# USB_Adapter.net
KiCad netlist of a schematic drawn in EAGLE
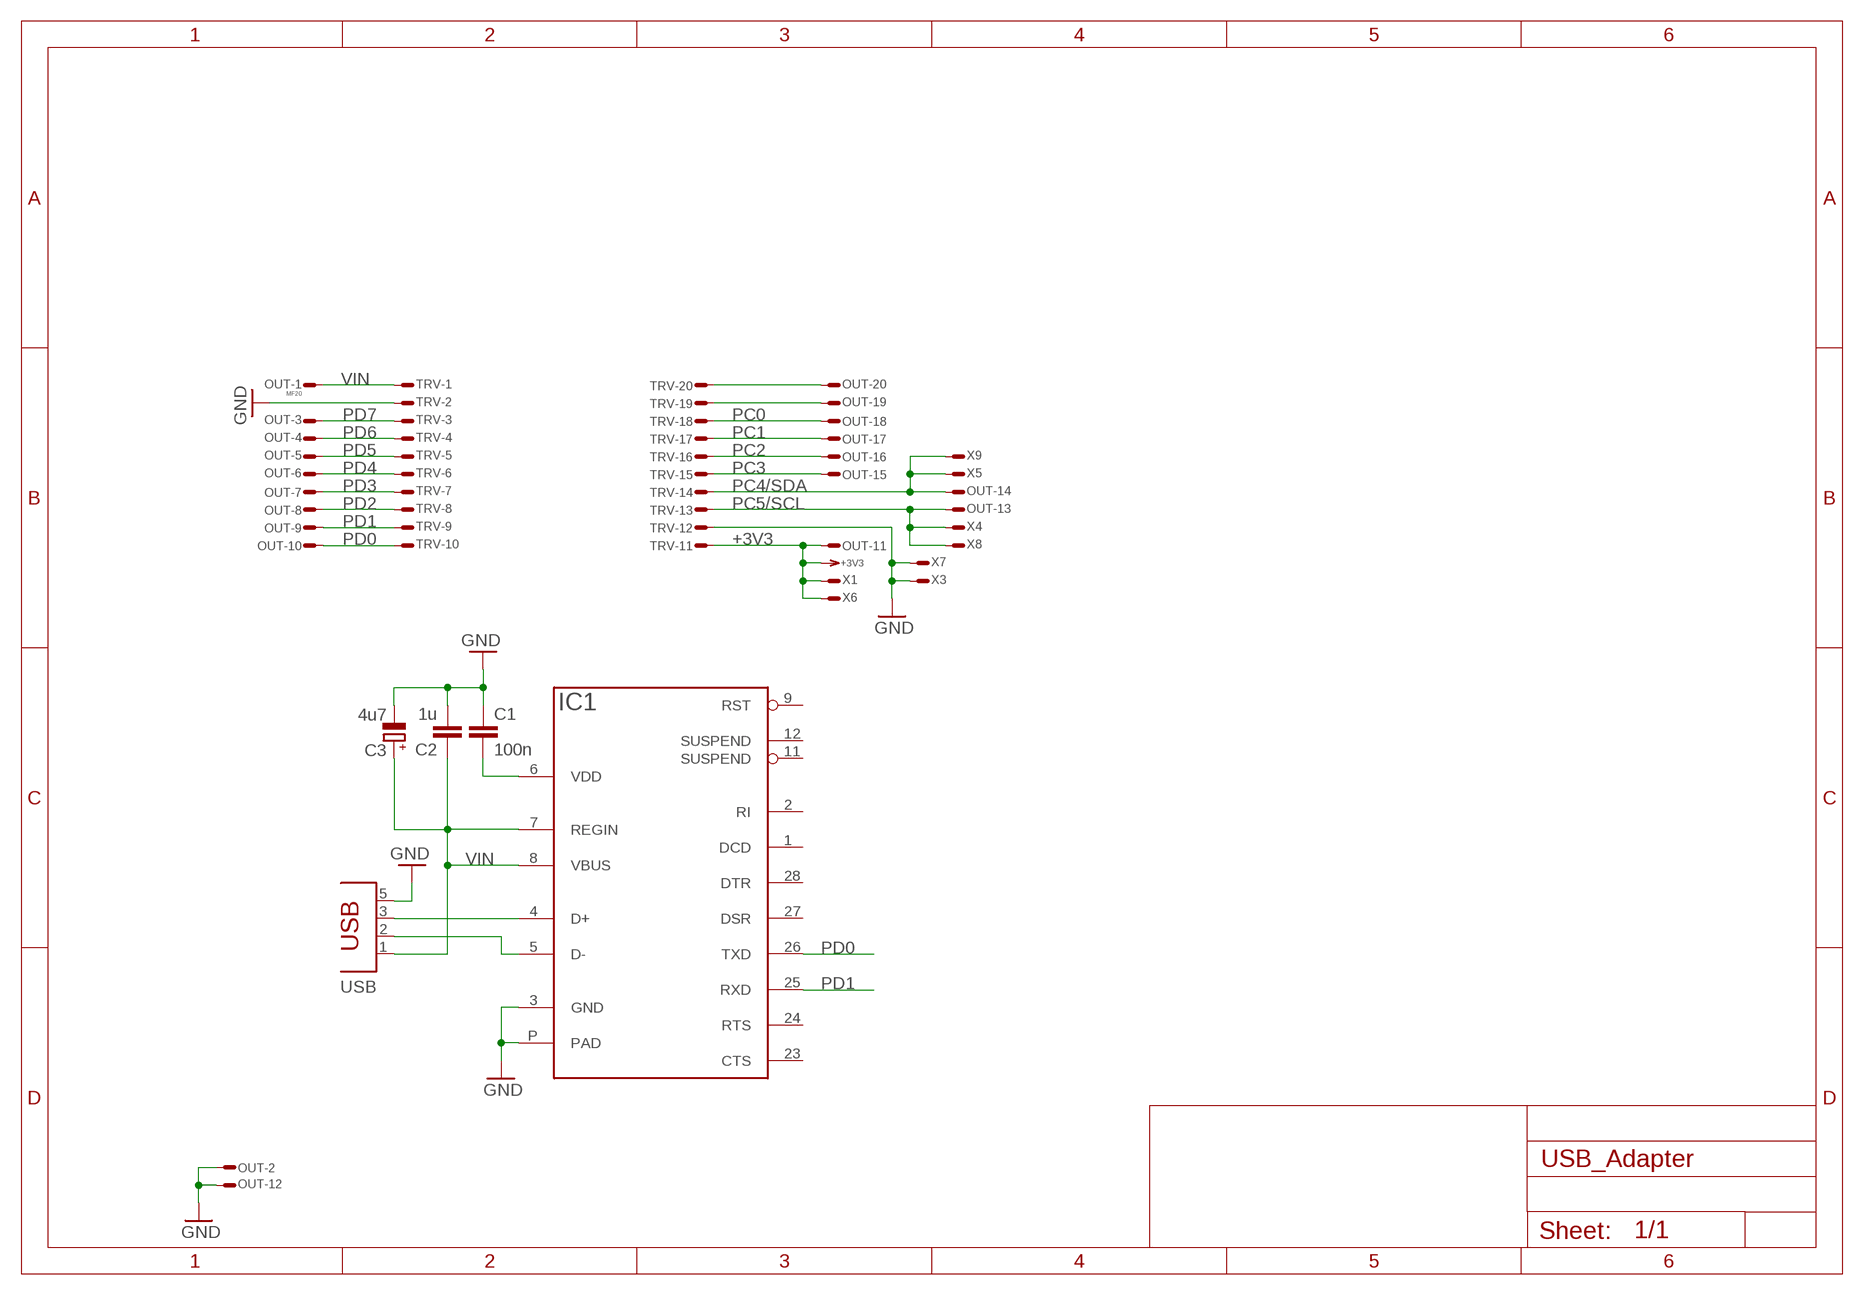
[diagram p0: schematic, sheet 1]

(export (version "E")
  (design (tool "Eeschema 10.0.6"))
  (components
    (comp (ref "C1")
      (value "100n")
      (footprint "eagle-import:0603")
      (libsource (lib "eagle-import") (part "C0603"))
    )
    (comp (ref "C2")
      (value "1u")
      (footprint "eagle-import:0603")
      (libsource (lib "eagle-import") (part "C0603"))
    )
    (comp (ref "C3")
      (value "4u7")
      (footprint "eagle-import:SMC_A")
      (libsource (lib "eagle-import") (part "C_POLSMCA"))
    )
    (comp (ref "IC1")
      (value "CP2102")
      (footprint "eagle-import:QFN28")
      (libsource (lib "eagle-import") (part "CP2102"))
    )
    (comp (ref "OUT")
      (value "MF20")
      (footprint "eagle-import:ML20S")
      (libsource (lib "eagle-import") (part "ML20?ES"))
    )
    (comp (ref "TRV")
      (value "ML20SE")
      (footprint "eagle-import:ML20S")
      (libsource (lib "eagle-import") (part "ML20?ES"))
    )
    (comp (ref "USB")
      (value "USBBM")
      (footprint "eagle-import:USB-BM")
      (libsource (lib "eagle-import") (part "USBBM"))
    )
    (comp (ref "X1")
      (value "WIREPADT1.6/0.9")
      (footprint "eagle-import:T1.6_0.9")
      (libsource (lib "eagle-import") (part "WIREPADT1.6/0.9"))
    )
    (comp (ref "X3")
      (value "WIREPADT1.6/0.9")
      (footprint "eagle-import:T1.6_0.9")
      (libsource (lib "eagle-import") (part "WIREPADT1.6/0.9"))
    )
    (comp (ref "X4")
      (value "WIREPADT1.6/0.9")
      (footprint "eagle-import:T1.6_0.9")
      (libsource (lib "eagle-import") (part "WIREPADT1.6/0.9"))
    )
    (comp (ref "X5")
      (value "WIREPADT1.6/0.9")
      (footprint "eagle-import:T1.6_0.9")
      (libsource (lib "eagle-import") (part "WIREPADT1.6/0.9"))
    )
    (comp (ref "X6")
      (value "WIREPADT1.6/0.9")
      (footprint "eagle-import:T1.6_0.9")
      (libsource (lib "eagle-import") (part "WIREPADT1.6/0.9"))
    )
    (comp (ref "X7")
      (value "WIREPADT1.6/0.9")
      (footprint "eagle-import:T1.6_0.9")
      (libsource (lib "eagle-import") (part "WIREPADT1.6/0.9"))
    )
    (comp (ref "X8")
      (value "WIREPADT1.6/0.9")
      (footprint "eagle-import:T1.6_0.9")
      (libsource (lib "eagle-import") (part "WIREPADT1.6/0.9"))
    )
    (comp (ref "X9")
      (value "WIREPADT1.6/0.9")
      (footprint "eagle-import:T1.6_0.9")
      (libsource (lib "eagle-import") (part "WIREPADT1.6/0.9"))
    )
  )
  (nets
    (net (code "1") (name "+3V3") (class "Default")
      (node (ref "OUT") (pin "11") (pinfunction "S_11") (pintype "passive"))
      (node (ref "TRV") (pin "11") (pinfunction "S_11") (pintype "passive"))
      (node (ref "X1") (pin "1") (pinfunction "S_1") (pintype "passive"))
      (node (ref "X6") (pin "1") (pinfunction "S_1") (pintype "passive"))
    )
    (net (code "2") (name "/PC0") (class "Default")
      (node (ref "OUT") (pin "18") (pinfunction "S_18") (pintype "passive"))
      (node (ref "TRV") (pin "18") (pinfunction "S_18") (pintype "passive"))
    )
    (net (code "3") (name "/PC1") (class "Default")
      (node (ref "OUT") (pin "17") (pinfunction "S_17") (pintype "passive"))
      (node (ref "TRV") (pin "17") (pinfunction "S_17") (pintype "passive"))
    )
    (net (code "4") (name "/PC2") (class "Default")
      (node (ref "OUT") (pin "16") (pinfunction "S_16") (pintype "passive"))
      (node (ref "TRV") (pin "16") (pinfunction "S_16") (pintype "passive"))
    )
    (net (code "5") (name "/PC3") (class "Default")
      (node (ref "OUT") (pin "15") (pinfunction "S_15") (pintype "passive"))
      (node (ref "TRV") (pin "15") (pinfunction "S_15") (pintype "passive"))
    )
    (net (code "6") (name "/PC4{slash}SDA") (class "Default")
      (node (ref "OUT") (pin "14") (pinfunction "S_14") (pintype "passive"))
      (node (ref "TRV") (pin "14") (pinfunction "S_14") (pintype "passive"))
      (node (ref "X5") (pin "1") (pinfunction "S_1") (pintype "passive"))
      (node (ref "X9") (pin "1") (pinfunction "S_1") (pintype "passive"))
    )
    (net (code "7") (name "/PC5{slash}SCL") (class "Default")
      (node (ref "OUT") (pin "13") (pinfunction "S_13") (pintype "passive"))
      (node (ref "TRV") (pin "13") (pinfunction "S_13") (pintype "passive"))
      (node (ref "X4") (pin "1") (pinfunction "S_1") (pintype "passive"))
      (node (ref "X8") (pin "1") (pinfunction "S_1") (pintype "passive"))
    )
    (net (code "8") (name "/PD0") (class "Default")
      (node (ref "IC1") (pin "26") (pinfunction "TXD_26") (pintype "output"))
      (node (ref "OUT") (pin "10") (pinfunction "S_10") (pintype "passive"))
      (node (ref "TRV") (pin "10") (pinfunction "S_10") (pintype "passive"))
    )
    (net (code "9") (name "/PD1") (class "Default")
      (node (ref "IC1") (pin "25") (pinfunction "RXD_25") (pintype "input"))
      (node (ref "OUT") (pin "9") (pinfunction "S_9") (pintype "passive"))
      (node (ref "TRV") (pin "9") (pinfunction "S_9") (pintype "passive"))
    )
    (net (code "10") (name "/PD2") (class "Default")
      (node (ref "OUT") (pin "8") (pinfunction "S_8") (pintype "passive"))
      (node (ref "TRV") (pin "8") (pinfunction "S_8") (pintype "passive"))
    )
    (net (code "11") (name "/PD3") (class "Default")
      (node (ref "OUT") (pin "7") (pinfunction "S_7") (pintype "passive"))
      (node (ref "TRV") (pin "7") (pinfunction "S_7") (pintype "passive"))
    )
    (net (code "12") (name "/PD4") (class "Default")
      (node (ref "OUT") (pin "6") (pinfunction "S_6") (pintype "passive"))
      (node (ref "TRV") (pin "6") (pinfunction "S_6") (pintype "passive"))
    )
    (net (code "13") (name "/PD5") (class "Default")
      (node (ref "OUT") (pin "5") (pinfunction "S_5") (pintype "passive"))
      (node (ref "TRV") (pin "5") (pinfunction "S_5") (pintype "passive"))
    )
    (net (code "14") (name "/PD6") (class "Default")
      (node (ref "OUT") (pin "4") (pinfunction "S_4") (pintype "passive"))
      (node (ref "TRV") (pin "4") (pinfunction "S_4") (pintype "passive"))
    )
    (net (code "15") (name "/PD7") (class "Default")
      (node (ref "OUT") (pin "3") (pinfunction "S_3") (pintype "passive"))
      (node (ref "TRV") (pin "3") (pinfunction "S_3") (pintype "passive"))
    )
    (net (code "16") (name "/VIN") (class "Default")
      (node (ref "C2") (pin "1") (pinfunction "1_1") (pintype "passive"))
      (node (ref "C3") (pin "+") (pinfunction "+_+") (pintype "passive"))
      (node (ref "IC1") (pin "7") (pinfunction "REGIN_7") (pintype "input"))
      (node (ref "IC1") (pin "8") (pinfunction "VBUS_8") (pintype "input"))
      (node (ref "OUT") (pin "1") (pinfunction "S_1") (pintype "passive"))
      (node (ref "TRV") (pin "1") (pinfunction "S_1") (pintype "passive"))
      (node (ref "USB") (pin "1") (pinfunction "VCC_1") (pintype "bidirectional"))
    )
    (net (code "17") (name "GND") (class "Default")
      (node (ref "C1") (pin "1") (pinfunction "1_1") (pintype "passive"))
      (node (ref "C2") (pin "2") (pinfunction "2_2") (pintype "passive"))
      (node (ref "C3") (pin "-") (pinfunction "-_-") (pintype "passive"))
      (node (ref "IC1") (pin "3") (pinfunction "GND_3") (pintype "power_in"))
      (node (ref "IC1") (pin "P") (pinfunction "PAD_P") (pintype "power_in"))
      (node (ref "OUT") (pin "12") (pinfunction "S_12") (pintype "passive"))
      (node (ref "OUT") (pin "2") (pinfunction "S_2") (pintype "passive"))
      (node (ref "TRV") (pin "12") (pinfunction "S_12") (pintype "passive"))
      (node (ref "TRV") (pin "2") (pinfunction "S_2") (pintype "passive"))
      (node (ref "USB") (pin "5") (pinfunction "GND_5") (pintype "bidirectional"))
      (node (ref "X3") (pin "1") (pinfunction "S_1") (pintype "passive"))
      (node (ref "X7") (pin "1") (pinfunction "S_1") (pintype "passive"))
    )
    (net (code "18") (name "Net-(IC1-D+)") (class "Default")
      (node (ref "IC1") (pin "4") (pinfunction "D+_4") (pintype "bidirectional"))
      (node (ref "USB") (pin "3") (pinfunction "D+_3") (pintype "bidirectional"))
    )
    (net (code "19") (name "Net-(IC1-D-)") (class "Default")
      (node (ref "IC1") (pin "5") (pinfunction "D-_5") (pintype "bidirectional"))
      (node (ref "USB") (pin "2") (pinfunction "D-_2") (pintype "bidirectional"))
    )
    (net (code "20") (name "Net-(IC1-VDD)") (class "Default")
      (node (ref "C1") (pin "2") (pinfunction "2_2") (pintype "passive"))
      (node (ref "IC1") (pin "6") (pinfunction "VDD_6") (pintype "passive"))
    )
    (net (code "21") (name "Net-(OUTK-S)") (class "Default")
      (node (ref "OUT") (pin "19") (pinfunction "S_19") (pintype "passive"))
      (node (ref "TRV") (pin "19") (pinfunction "S_19") (pintype "passive"))
    )
    (net (code "22") (name "Net-(OUTM-S)") (class "Default")
      (node (ref "OUT") (pin "20") (pinfunction "S_20") (pintype "passive"))
      (node (ref "TRV") (pin "20") (pinfunction "S_20") (pintype "passive"))
    )
    (net (code "23") (name "unconnected-(IC1-CTS-Pad23)") (class "Default")
      (node (ref "IC1") (pin "23") (pinfunction "CTS_23") (pintype "input"))
    )
    (net (code "24") (name "unconnected-(IC1-DCD-Pad1)") (class "Default")
      (node (ref "IC1") (pin "1") (pinfunction "DCD_1") (pintype "input"))
    )
    (net (code "25") (name "unconnected-(IC1-DSR-Pad27)") (class "Default")
      (node (ref "IC1") (pin "27") (pinfunction "DSR_27") (pintype "input"))
    )
    (net (code "26") (name "unconnected-(IC1-DTR-Pad28)") (class "Default")
      (node (ref "IC1") (pin "28") (pinfunction "DTR_28") (pintype "output"))
    )
    (net (code "27") (name "unconnected-(IC1-RI-Pad2)") (class "Default")
      (node (ref "IC1") (pin "2") (pinfunction "RI_2") (pintype "input"))
    )
    (net (code "28") (name "unconnected-(IC1-RST-Pad9)") (class "Default")
      (node (ref "IC1") (pin "9") (pinfunction "RST_9") (pintype "bidirectional"))
    )
    (net (code "29") (name "unconnected-(IC1-RTS-Pad24)") (class "Default")
      (node (ref "IC1") (pin "24") (pinfunction "RTS_24") (pintype "output"))
    )
    (net (code "30") (name "unconnected-(IC1-SUSPEND-Pad11)") (class "Default")
      (node (ref "IC1") (pin "11") (pinfunction "SUSPEND_11") (pintype "output"))
    )
    (net (code "31") (name "unconnected-(IC1-SUSPEND-Pad12)") (class "Default")
      (node (ref "IC1") (pin "12") (pinfunction "SUSPEND_12") (pintype "output"))
    )
  )
)
